# ArduboyBoard.net
KiCad netlist of a schematic drawn in EAGLE
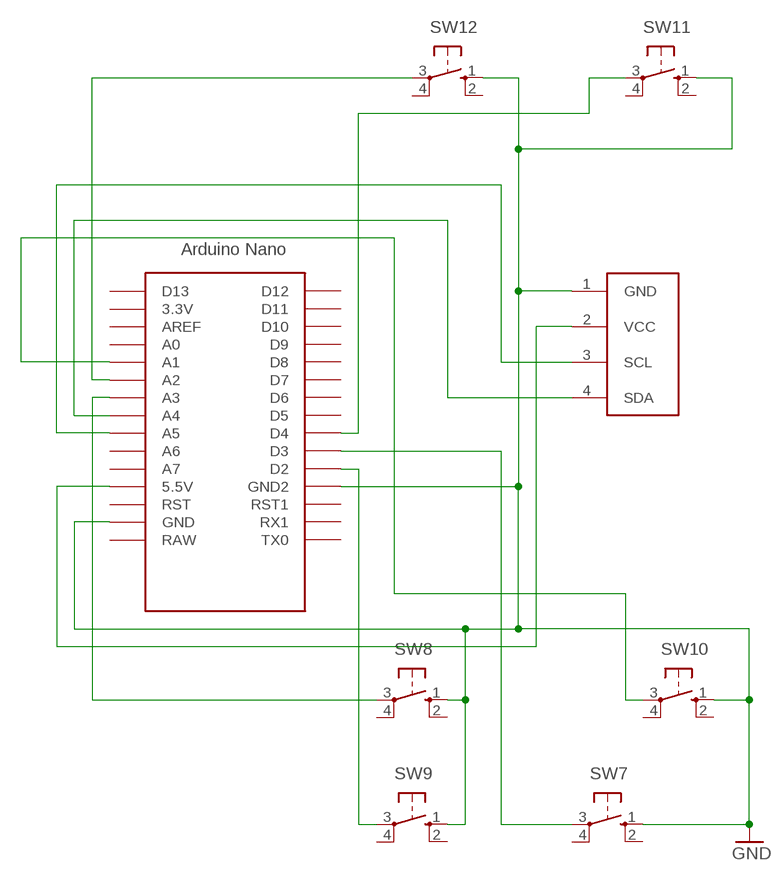
[diagram p0: schematic, sheet 1]

(export (version "E")
  (design (tool "Eeschema 10.0.6"))
  (components
    (comp (ref "SW7")
      (value "10-XX")
      (footprint "eagle-import:B3F-10XX")
      (libsource (lib "eagle-import") (part "10-XX"))
    )
    (comp (ref "SW8")
      (value "10-XX")
      (footprint "eagle-import:B3F-10XX")
      (libsource (lib "eagle-import") (part "10-XX"))
    )
    (comp (ref "SW9")
      (value "10-XX")
      (footprint "eagle-import:B3F-10XX")
      (libsource (lib "eagle-import") (part "10-XX"))
    )
    (comp (ref "SW10")
      (value "10-XX")
      (footprint "eagle-import:B3F-10XX")
      (libsource (lib "eagle-import") (part "10-XX"))
    )
    (comp (ref "SW11")
      (value "10-XX")
      (footprint "eagle-import:B3F-10XX")
      (libsource (lib "eagle-import") (part "10-XX"))
    )
    (comp (ref "SW12")
      (value "10-XX")
      (footprint "eagle-import:B3F-10XX")
      (libsource (lib "eagle-import") (part "10-XX"))
    )
    (comp (ref "U$1")
      (value "NANO")
      (footprint "eagle-import:NANO")
      (libsource (lib "eagle-import") (part "NANO"))
    )
    (comp (ref "U$2")
      (value "I2C_OLED")
      (footprint "eagle-import:I2C_OLED_PACKAGE")
      (libsource (lib "eagle-import") (part "I2C_OLED"))
    )
  )
  (nets
    (net (code "1") (name "GND") (class "Default")
      (node (ref "SW10") (pin "1") (pinfunction "S_1") (pintype "passive"))
      (node (ref "SW11") (pin "1") (pinfunction "S_1") (pintype "passive"))
      (node (ref "SW12") (pin "1") (pinfunction "S_1") (pintype "passive"))
      (node (ref "SW7") (pin "1") (pinfunction "S_1") (pintype "passive"))
      (node (ref "SW8") (pin "1") (pinfunction "S_1") (pintype "passive"))
      (node (ref "SW9") (pin "1") (pinfunction "S_1") (pintype "passive"))
      (node (ref "U$1") (pin "GND") (pinfunction "GND_GND") (pintype "bidirectional"))
      (node (ref "U$1") (pin "GND1") (pinfunction "GND2_GND1") (pintype "bidirectional"))
      (node (ref "U$2") (pin "1") (pinfunction "GND_1") (pintype "bidirectional"))
    )
    (net (code "2") (name "Net-(SW7-P)") (class "Default")
      (node (ref "SW7") (pin "3") (pinfunction "P_3") (pintype "passive"))
      (node (ref "U$1") (pin "D3") (pinfunction "D3_D3") (pintype "bidirectional"))
    )
    (net (code "3") (name "Net-(SW8-P)") (class "Default")
      (node (ref "SW8") (pin "3") (pinfunction "P_3") (pintype "passive"))
      (node (ref "U$1") (pin "A3") (pinfunction "A3_A3") (pintype "bidirectional"))
    )
    (net (code "4") (name "Net-(SW9-P)") (class "Default")
      (node (ref "SW9") (pin "3") (pinfunction "P_3") (pintype "passive"))
      (node (ref "U$1") (pin "D2") (pinfunction "D2_D2") (pintype "bidirectional"))
    )
    (net (code "5") (name "Net-(SW10-P)") (class "Default")
      (node (ref "SW10") (pin "3") (pinfunction "P_3") (pintype "passive"))
      (node (ref "U$1") (pin "A1") (pinfunction "A1_A1") (pintype "bidirectional"))
    )
    (net (code "6") (name "Net-(SW11-P)") (class "Default")
      (node (ref "SW11") (pin "3") (pinfunction "P_3") (pintype "passive"))
      (node (ref "U$1") (pin "D4") (pinfunction "D4_D4") (pintype "bidirectional"))
    )
    (net (code "7") (name "Net-(SW12-P)") (class "Default")
      (node (ref "SW12") (pin "3") (pinfunction "P_3") (pintype "passive"))
      (node (ref "U$1") (pin "A2") (pinfunction "A2_A2") (pintype "bidirectional"))
    )
    (net (code "8") (name "Net-(U$1-5.5V)") (class "Default")
      (node (ref "U$1") (pin "5V") (pinfunction "5.5V_5V") (pintype "bidirectional"))
      (node (ref "U$2") (pin "2") (pinfunction "VCC_2") (pintype "bidirectional"))
    )
    (net (code "9") (name "Net-(U$2-SCL)") (class "Default")
      (node (ref "U$1") (pin "A5") (pinfunction "A5_A5") (pintype "bidirectional"))
      (node (ref "U$2") (pin "3") (pinfunction "SCL_3") (pintype "bidirectional"))
    )
    (net (code "10") (name "Net-(U$2-SDA)") (class "Default")
      (node (ref "U$1") (pin "A4") (pinfunction "A4_A4") (pintype "bidirectional"))
      (node (ref "U$2") (pin "4") (pinfunction "SDA_4") (pintype "bidirectional"))
    )
    (net (code "11") (name "unconnected-(SW7-P1-Pad4)") (class "Default")
      (node (ref "SW7") (pin "4") (pinfunction "P1_4") (pintype "passive"))
    )
    (net (code "12") (name "unconnected-(SW7-S1-Pad2)") (class "Default")
      (node (ref "SW7") (pin "2") (pinfunction "S1_2") (pintype "passive"))
    )
    (net (code "13") (name "unconnected-(SW8-P1-Pad4)") (class "Default")
      (node (ref "SW8") (pin "4") (pinfunction "P1_4") (pintype "passive"))
    )
    (net (code "14") (name "unconnected-(SW8-S1-Pad2)") (class "Default")
      (node (ref "SW8") (pin "2") (pinfunction "S1_2") (pintype "passive"))
    )
    (net (code "15") (name "unconnected-(SW9-P1-Pad4)") (class "Default")
      (node (ref "SW9") (pin "4") (pinfunction "P1_4") (pintype "passive"))
    )
    (net (code "16") (name "unconnected-(SW9-S1-Pad2)") (class "Default")
      (node (ref "SW9") (pin "2") (pinfunction "S1_2") (pintype "passive"))
    )
    (net (code "17") (name "unconnected-(SW10-P1-Pad4)") (class "Default")
      (node (ref "SW10") (pin "4") (pinfunction "P1_4") (pintype "passive"))
    )
    (net (code "18") (name "unconnected-(SW10-S1-Pad2)") (class "Default")
      (node (ref "SW10") (pin "2") (pinfunction "S1_2") (pintype "passive"))
    )
    (net (code "19") (name "unconnected-(SW11-P1-Pad4)") (class "Default")
      (node (ref "SW11") (pin "4") (pinfunction "P1_4") (pintype "passive"))
    )
    (net (code "20") (name "unconnected-(SW11-S1-Pad2)") (class "Default")
      (node (ref "SW11") (pin "2") (pinfunction "S1_2") (pintype "passive"))
    )
    (net (code "21") (name "unconnected-(SW12-P1-Pad4)") (class "Default")
      (node (ref "SW12") (pin "4") (pinfunction "P1_4") (pintype "passive"))
    )
    (net (code "22") (name "unconnected-(SW12-S1-Pad2)") (class "Default")
      (node (ref "SW12") (pin "2") (pinfunction "S1_2") (pintype "passive"))
    )
    (net (code "23") (name "unconnected-(U$1-Pad3.3V)") (class "Default")
      (node (ref "U$1") (pin "3.3V") (pinfunction "3.3V_3.3V") (pintype "bidirectional"))
    )
    (net (code "24") (name "unconnected-(U$1-PadA0)") (class "Default")
      (node (ref "U$1") (pin "A0") (pinfunction "A0_A0") (pintype "bidirectional"))
    )
    (net (code "25") (name "unconnected-(U$1-PadA6)") (class "Default")
      (node (ref "U$1") (pin "A6") (pinfunction "A6_A6") (pintype "bidirectional"))
    )
    (net (code "26") (name "unconnected-(U$1-PadA7)") (class "Default")
      (node (ref "U$1") (pin "A7") (pinfunction "A7_A7") (pintype "bidirectional"))
    )
    (net (code "27") (name "unconnected-(U$1-PadAREF)") (class "Default")
      (node (ref "U$1") (pin "AREF") (pinfunction "AREF_AREF") (pintype "bidirectional"))
    )
    (net (code "28") (name "unconnected-(U$1-PadD5)") (class "Default")
      (node (ref "U$1") (pin "D5") (pinfunction "D5_D5") (pintype "bidirectional"))
    )
    (net (code "29") (name "unconnected-(U$1-PadD6)") (class "Default")
      (node (ref "U$1") (pin "D6") (pinfunction "D6_D6") (pintype "bidirectional"))
    )
    (net (code "30") (name "unconnected-(U$1-PadD7)") (class "Default")
      (node (ref "U$1") (pin "D7") (pinfunction "D7_D7") (pintype "bidirectional"))
    )
    (net (code "31") (name "unconnected-(U$1-PadD8)") (class "Default")
      (node (ref "U$1") (pin "D8") (pinfunction "D8_D8") (pintype "bidirectional"))
    )
    (net (code "32") (name "unconnected-(U$1-PadD9)") (class "Default")
      (node (ref "U$1") (pin "D9") (pinfunction "D9_D9") (pintype "bidirectional"))
    )
    (net (code "33") (name "unconnected-(U$1-PadD10)") (class "Default")
      (node (ref "U$1") (pin "D10") (pinfunction "D10_D10") (pintype "bidirectional"))
    )
    (net (code "34") (name "unconnected-(U$1-PadD11)") (class "Default")
      (node (ref "U$1") (pin "D11") (pinfunction "D11_D11") (pintype "bidirectional"))
    )
    (net (code "35") (name "unconnected-(U$1-PadD12)") (class "Default")
      (node (ref "U$1") (pin "D12") (pinfunction "D12_D12") (pintype "bidirectional"))
    )
    (net (code "36") (name "unconnected-(U$1-PadD13)") (class "Default")
      (node (ref "U$1") (pin "D13") (pinfunction "D13_D13") (pintype "bidirectional"))
    )
    (net (code "37") (name "unconnected-(U$1-PadICSP1)") (class "Default")
      (node (ref "U$1") (pin "ICSP1") (pinfunction "ICSP1_ICSP1") (pintype "bidirectional"))
    )
    (net (code "38") (name "unconnected-(U$1-PadICSP2)") (class "Default")
      (node (ref "U$1") (pin "ICSP2") (pinfunction "ICSP2_ICSP2") (pintype "bidirectional"))
    )
    (net (code "39") (name "unconnected-(U$1-PadICSP3)") (class "Default")
      (node (ref "U$1") (pin "ICSP3") (pinfunction "ICSP3_ICSP3") (pintype "bidirectional"))
    )
    (net (code "40") (name "unconnected-(U$1-PadICSP4)") (class "Default")
      (node (ref "U$1") (pin "ICSP4") (pinfunction "ICSP4_ICSP4") (pintype "bidirectional"))
    )
    (net (code "41") (name "unconnected-(U$1-PadICSP5)") (class "Default")
      (node (ref "U$1") (pin "ICSP5") (pinfunction "ICSP5_ICSP5") (pintype "bidirectional"))
    )
    (net (code "42") (name "unconnected-(U$1-PadICSP6)") (class "Default")
      (node (ref "U$1") (pin "ICSP6") (pinfunction "ICSP6_ICSP6") (pintype "bidirectional"))
    )
    (net (code "43") (name "unconnected-(U$1-PadRAW)") (class "Default")
      (node (ref "U$1") (pin "RAW") (pinfunction "RAW_RAW") (pintype "bidirectional"))
    )
    (net (code "44") (name "unconnected-(U$1-PadRST)") (class "Default")
      (node (ref "U$1") (pin "RST") (pinfunction "RST_RST") (pintype "bidirectional"))
    )
    (net (code "45") (name "unconnected-(U$1-PadRST1)") (class "Default")
      (node (ref "U$1") (pin "RST1") (pinfunction "RST1_RST1") (pintype "bidirectional"))
    )
    (net (code "46") (name "unconnected-(U$1-PadRX1)") (class "Default")
      (node (ref "U$1") (pin "RX1") (pinfunction "RX1_RX1") (pintype "bidirectional"))
    )
    (net (code "47") (name "unconnected-(U$1-PadTX0)") (class "Default")
      (node (ref "U$1") (pin "TX0") (pinfunction "TX0_TX0") (pintype "bidirectional"))
    )
  )
)
